# MCU.net
KiCad netlist of a schematic drawn in Altium Designer
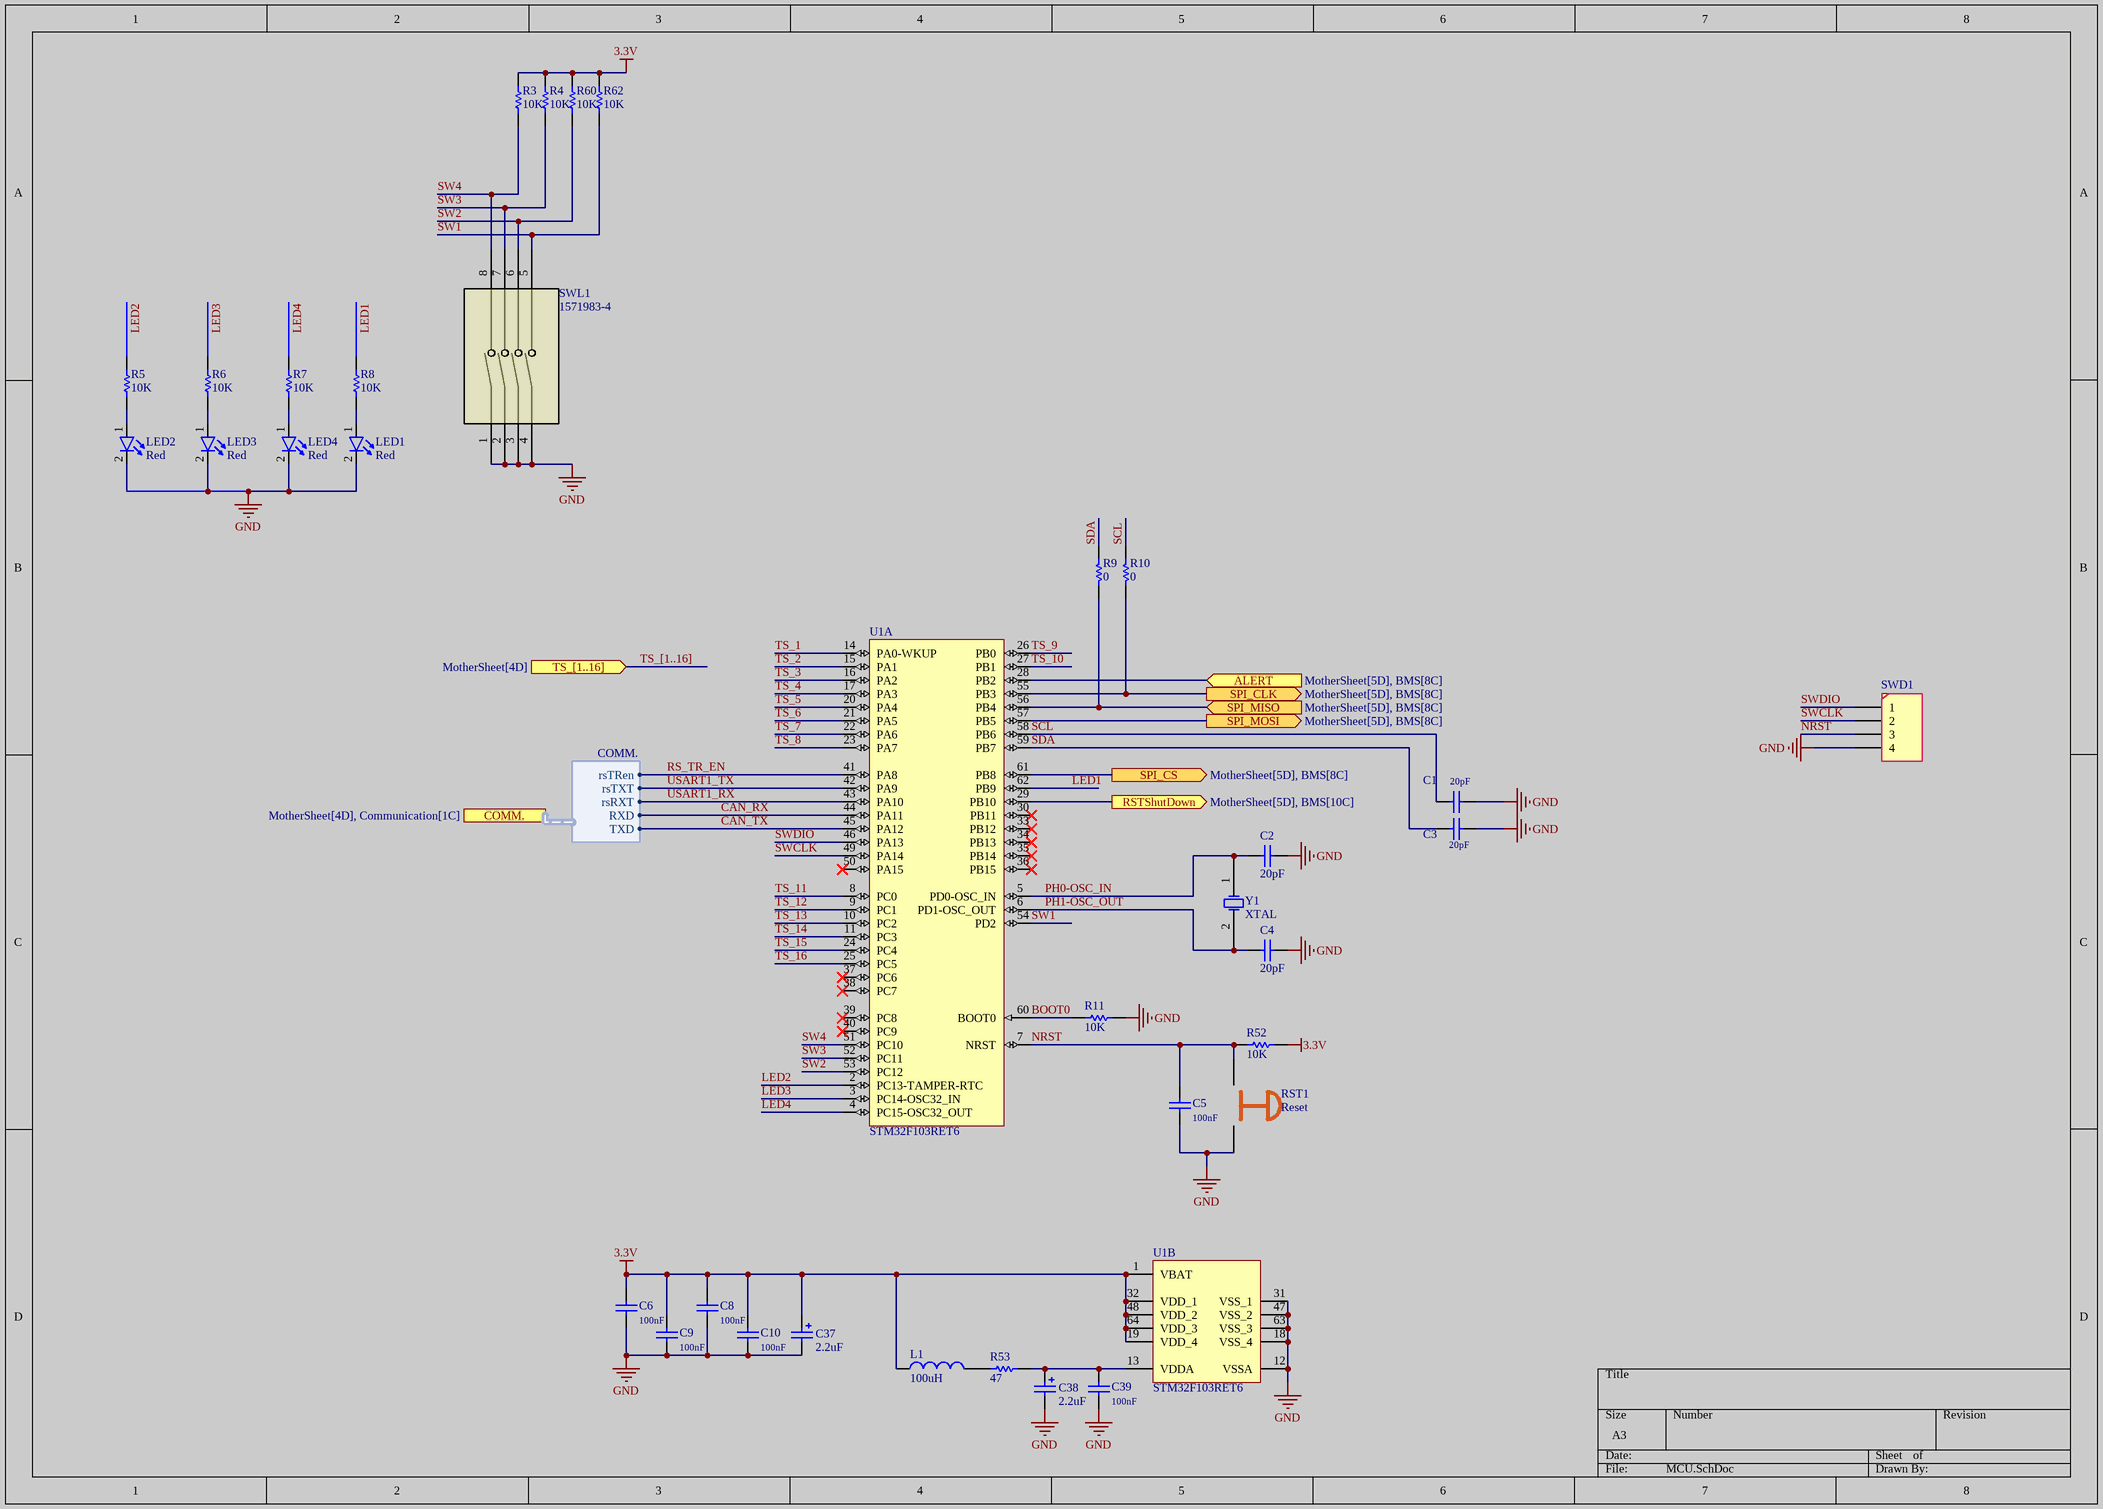
[diagram p0: MCU.SchDoc]

(export (version "E")
  (design (tool "Eeschema 10.0.6"))
  (components
    (comp (ref "C1")
      (value "20pF")
      (footprint "CAPC0603")
      (description "Capacitor")
      (fields (field (name "PUBLISHER") "Altium Limited"))
      (libsource (lib "eLIB") (part "Capacitor"))
    )
    (comp (ref "C2")
      (value "20pF")
      (footprint "CAPC0603")
      (description "Capacitor")
      (fields (field (name "PUBLISHER") "Altium Limited"))
      (libsource (lib "eLIB") (part "Capacitor"))
    )
    (comp (ref "C3")
      (value "20pF")
      (footprint "CAPC0603")
      (description "Capacitor")
      (fields (field (name "PUBLISHER") "Altium Limited"))
      (libsource (lib "eLIB") (part "Capacitor"))
    )
    (comp (ref "C4")
      (value "20pF")
      (footprint "CAPC0603")
      (description "Capacitor")
      (fields (field (name "PUBLISHER") "Altium Limited"))
      (libsource (lib "eLIB") (part "Capacitor"))
    )
    (comp (ref "C5")
      (value "100nF")
      (footprint "CAPC0603")
      (description "Capacitor")
      (fields (field (name "PUBLISHER") "Altium Limited"))
      (libsource (lib "eLIB") (part "Capacitor"))
    )
    (comp (ref "C6")
      (value "100nF")
      (footprint "CAPC0603")
      (description "Capacitor")
      (fields (field (name "PUBLISHER") "Altium Limited"))
      (libsource (lib "eLIB") (part "Capacitor"))
    )
    (comp (ref "C8")
      (value "100nF")
      (footprint "CAPC0603")
      (description "Capacitor")
      (fields (field (name "PUBLISHER") "Altium Limited"))
      (libsource (lib "eLIB") (part "Capacitor"))
    )
    (comp (ref "C9")
      (value "100nF")
      (footprint "CAPC0603")
      (description "Capacitor")
      (fields (field (name "PUBLISHER") "Altium Limited"))
      (libsource (lib "eLIB") (part "Capacitor"))
    )
    (comp (ref "C10")
      (value "100nF")
      (footprint "CAPC0603")
      (description "Capacitor")
      (fields (field (name "PUBLISHER") "Altium Limited"))
      (libsource (lib "eLIB") (part "Capacitor"))
    )
    (comp (ref "C37")
      (value "2.2uF")
      (footprint "CAP1206")
      (description "Tantalium Capacitor Size C")
      (fields (field (name "PUBLISHER") "Altium Limited"))
      (libsource (lib "eLIB") (part "Cap_Tan"))
    )
    (comp (ref "C38")
      (value "2.2uF")
      (footprint "CAP1206")
      (description "Tantalium Capacitor Size C")
      (fields (field (name "PUBLISHER") "Altium Limited"))
      (libsource (lib "eLIB") (part "Cap_Tan"))
    )
    (comp (ref "C39")
      (value "100nF")
      (footprint "CAPC0603")
      (description "Capacitor")
      (fields (field (name "PUBLISHER") "Altium Limited"))
      (libsource (lib "eLIB") (part "Capacitor"))
    )
    (comp (ref "L1")
      (value "100uH")
      (footprint "RES1206")
      (fields (field (name "PUBLISHER") "Altium Limited"))
      (libsource (lib "eLIB") (part "INDUCTOR"))
    )
    (comp (ref "LED1")
      (value "Red")
      (footprint "LED")
      (description "LED")
      (fields (field (name "COLOR") "Red") (field (name "DESIGNER") "Saeid Jorablo"))
      (libsource (lib "TaraSchlib") (part "LED"))
    )
    (comp (ref "LED2")
      (value "Red")
      (footprint "LED")
      (description "LED")
      (fields (field (name "COLOR") "Red") (field (name "DESIGNER") "Saeid Jorablo"))
      (libsource (lib "TaraSchlib") (part "LED"))
    )
    (comp (ref "LED3")
      (value "Red")
      (footprint "LED")
      (description "LED")
      (fields (field (name "COLOR") "Red") (field (name "DESIGNER") "Saeid Jorablo"))
      (libsource (lib "TaraSchlib") (part "LED"))
    )
    (comp (ref "LED4")
      (value "Red")
      (footprint "LED")
      (description "LED")
      (fields (field (name "COLOR") "Red") (field (name "DESIGNER") "Saeid Jorablo"))
      (libsource (lib "TaraSchlib") (part "LED"))
    )
    (comp (ref "R3")
      (value "10K")
      (footprint "RES0603")
      (description "0603,0.1W")
      (fields (field (name "PUBLISHER") "Altium Limited"))
      (libsource (lib "eLIB") (part "Resistor"))
    )
    (comp (ref "R4")
      (value "10K")
      (footprint "RES0603")
      (description "0603,0.1W")
      (fields (field (name "PUBLISHER") "Altium Limited"))
      (libsource (lib "eLIB") (part "Resistor"))
    )
    (comp (ref "R5")
      (value "10K")
      (footprint "RESC0603")
      (description "0603,0.1W")
      (fields (field (name "PUBLISHER") "Altium Limited"))
      (libsource (lib "eLIB") (part "Resistor"))
    )
    (comp (ref "R6")
      (value "10K")
      (footprint "RESC0603")
      (description "0603,0.1W")
      (fields (field (name "PUBLISHER") "Altium Limited"))
      (libsource (lib "eLIB") (part "Resistor"))
    )
    (comp (ref "R7")
      (value "10K")
      (footprint "RESC0603")
      (description "0603,0.1W")
      (fields (field (name "PUBLISHER") "Altium Limited"))
      (libsource (lib "eLIB") (part "Resistor"))
    )
    (comp (ref "R8")
      (value "10K")
      (footprint "RESC0603")
      (description "0603,0.1W")
      (fields (field (name "PUBLISHER") "Altium Limited"))
      (libsource (lib "eLIB") (part "Resistor"))
    )
    (comp (ref "R9")
      (value "0")
      (footprint "RESC0603")
      (description "0603,0.1W")
      (fields (field (name "PUBLISHER") "Altium Limited"))
      (libsource (lib "eLIB") (part "Resistor"))
    )
    (comp (ref "R10")
      (value "0")
      (footprint "RESC0603")
      (description "0603,0.1W")
      (fields (field (name "PUBLISHER") "Altium Limited"))
      (libsource (lib "eLIB") (part "Resistor"))
    )
    (comp (ref "R11")
      (value "10K")
      (footprint "RESC0603")
      (description "0603,0.1W")
      (fields (field (name "PUBLISHER") "Altium Limited"))
      (libsource (lib "eLIB") (part "Resistor"))
    )
    (comp (ref "R52")
      (value "10K")
      (footprint "RESC0603")
      (description "0603,0.1W")
      (fields (field (name "PUBLISHER") "Altium Limited"))
      (libsource (lib "eLIB") (part "Resistor"))
    )
    (comp (ref "R53")
      (value "47")
      (footprint "RESC0603")
      (description "0603,0.1W")
      (fields (field (name "PUBLISHER") "Altium Limited"))
      (libsource (lib "eLIB") (part "Resistor"))
    )
    (comp (ref "R60")
      (value "10K")
      (footprint "RES0603")
      (description "0603,0.1W")
      (fields (field (name "PUBLISHER") "Altium Limited"))
      (libsource (lib "eLIB") (part "Resistor"))
    )
    (comp (ref "R62")
      (value "10K")
      (footprint "RES0603")
      (description "0603,0.1W")
      (fields (field (name "PUBLISHER") "Altium Limited"))
      (libsource (lib "eLIB") (part "Resistor"))
    )
    (comp (ref "RST1")
      (value "Reset")
      (footprint "SWITCH-PB4")
      (description "4-Pin Push Button")
      (libsource (lib "eLIB") (part "Swtich-PB4"))
    )
    (comp (ref "SWD1")
      (value "~")
      (footprint "PIN HEADER 1*4 MALE")
      (description "Header, 4-Pin")
      (libsource (lib "eLIB") (part "Header1*4"))
    )
    (comp (ref "SWL1")
      (value "1571983-4")
      (footprint "SW4_1571983_4P_TEC")
      (description "GDH04S04=DIP SWITCH")
      (fields (field (name "COPYRIGHT") "Copyright (C) 2025 Ultra Librarian. All rights reserved."))
      (libsource (lib "SINA") (part "1571983-4"))
    )
    (comp (ref "U1")
      (value "STM32F103RET6")
      (footprint "LQFP, 64")
      (libsource (lib "SINA") (part "STM32F103RET6"))
    )
    (comp (ref "Y1") (value "XTAL") (footprint "XTAL") (libsource (lib "eLIB") (part "XTAL")))
  )
  (nets
    (net (code "2") (name "/ALERT") (class "Default")
      (node (ref "U1") (pin "28") (pinfunction "PB2_28") (pintype "bidirectional"))
    )
    (net (code "3") (name "/BOOT0") (class "Default")
      (node (ref "R11") (pin "2") (pinfunction "2_2") (pintype "passive"))
      (node (ref "U1") (pin "60") (pinfunction "BOOT0_60") (pintype "input"))
    )
    (net (code "4") (name "/CAN_RX") (class "Default")
      (node (ref "U1") (pin "44") (pinfunction "PA11_44") (pintype "bidirectional"))
    )
    (net (code "5") (name "/CAN_TX") (class "Default")
      (node (ref "U1") (pin "45") (pinfunction "PA12_45") (pintype "bidirectional"))
    )
    (net (code "6") (name "/LED1") (class "Default")
      (node (ref "R8") (pin "2") (pinfunction "2_2") (pintype "passive"))
      (node (ref "U1") (pin "62") (pinfunction "PB9_62") (pintype "bidirectional"))
    )
    (net (code "7") (name "/LED2") (class "Default")
      (node (ref "R5") (pin "2") (pinfunction "2_2") (pintype "passive"))
      (node (ref "U1") (pin "2") (pinfunction "PC13-TAMPER-RTC_2") (pintype "bidirectional"))
    )
    (net (code "8") (name "/LED3") (class "Default")
      (node (ref "R6") (pin "2") (pinfunction "2_2") (pintype "passive"))
      (node (ref "U1") (pin "3") (pinfunction "PC14-OSC32_IN_3") (pintype "bidirectional"))
    )
    (net (code "9") (name "/LED4") (class "Default")
      (node (ref "R7") (pin "2") (pinfunction "2_2") (pintype "passive"))
      (node (ref "U1") (pin "4") (pinfunction "PC15-OSC32_OUT_4") (pintype "bidirectional"))
    )
    (net (code "10") (name "/NRST") (class "Default")
      (node (ref "C5") (pin "1") (pinfunction "1_1") (pintype "passive"))
      (node (ref "R52") (pin "1") (pinfunction "1_1") (pintype "passive"))
      (node (ref "RST1") (pin "1") (pinfunction "1_1") (pintype "passive"))
      (node (ref "SWD1") (pin "3") (pinfunction "3_3") (pintype "passive"))
      (node (ref "U1") (pin "7") (pinfunction "NRST_7") (pintype "bidirectional"))
    )
    (net (code "11") (name "/PH0-OSC_IN") (class "Default")
      (node (ref "C2") (pin "2") (pinfunction "2_2") (pintype "passive"))
      (node (ref "U1") (pin "5") (pinfunction "PD0-OSC_IN_5") (pintype "bidirectional"))
      (node (ref "Y1") (pin "1") (pinfunction "1_1") (pintype "passive"))
    )
    (net (code "12") (name "/PH1-OSC_OUT") (class "Default")
      (node (ref "C4") (pin "2") (pinfunction "2_2") (pintype "passive"))
      (node (ref "U1") (pin "6") (pinfunction "PD1-OSC_OUT_6") (pintype "bidirectional"))
      (node (ref "Y1") (pin "2") (pinfunction "2_2") (pintype "passive"))
    )
    (net (code "13") (name "/RSTShutDown") (class "Default")
      (node (ref "U1") (pin "29") (pinfunction "PB10_29") (pintype "bidirectional"))
    )
    (net (code "14") (name "/RS_TR_EN") (class "Default")
      (node (ref "U1") (pin "41") (pinfunction "PA8_41") (pintype "bidirectional"))
    )
    (net (code "15") (name "/SCL") (class "Default")
      (node (ref "C1") (pin "1") (pinfunction "1_1") (pintype "passive"))
      (node (ref "R10") (pin "1") (pinfunction "1_1") (pintype "passive"))
      (node (ref "U1") (pin "58") (pinfunction "PB6_58") (pintype "bidirectional"))
    )
    (net (code "16") (name "/SDA") (class "Default")
      (node (ref "C3") (pin "1") (pinfunction "1_1") (pintype "passive"))
      (node (ref "R9") (pin "1") (pinfunction "1_1") (pintype "passive"))
      (node (ref "U1") (pin "59") (pinfunction "PB7_59") (pintype "bidirectional"))
    )
    (net (code "17") (name "/SPI_CLK") (class "Default")
      (node (ref "R10") (pin "2") (pinfunction "2_2") (pintype "passive"))
      (node (ref "U1") (pin "55") (pinfunction "PB3_55") (pintype "bidirectional"))
    )
    (net (code "18") (name "/SPI_CS") (class "Default")
      (node (ref "U1") (pin "61") (pinfunction "PB8_61") (pintype "bidirectional"))
    )
    (net (code "19") (name "/SPI_MISO") (class "Default")
      (node (ref "R9") (pin "2") (pinfunction "2_2") (pintype "passive"))
      (node (ref "U1") (pin "56") (pinfunction "PB4_56") (pintype "bidirectional"))
    )
    (net (code "20") (name "/SPI_MOSI") (class "Default")
      (node (ref "U1") (pin "57") (pinfunction "PB5_57") (pintype "bidirectional"))
    )
    (net (code "21") (name "/SW1") (class "Default")
      (node (ref "R62") (pin "1") (pinfunction "1_1") (pintype "passive"))
      (node (ref "SWL1") (pin "5") (pinfunction "5_5") (pintype "passive"))
      (node (ref "U1") (pin "54") (pinfunction "PD2_54") (pintype "bidirectional"))
    )
    (net (code "22") (name "/SW2") (class "Default")
      (node (ref "R60") (pin "1") (pinfunction "1_1") (pintype "passive"))
      (node (ref "SWL1") (pin "6") (pinfunction "6_6") (pintype "passive"))
      (node (ref "U1") (pin "53") (pinfunction "PC12_53") (pintype "bidirectional"))
    )
    (net (code "23") (name "/SW3") (class "Default")
      (node (ref "R4") (pin "1") (pinfunction "1_1") (pintype "passive"))
      (node (ref "SWL1") (pin "7") (pinfunction "7_7") (pintype "passive"))
      (node (ref "U1") (pin "52") (pinfunction "PC11_52") (pintype "bidirectional"))
    )
    (net (code "24") (name "/SW4") (class "Default")
      (node (ref "R3") (pin "1") (pinfunction "1_1") (pintype "passive"))
      (node (ref "SWL1") (pin "8") (pinfunction "8_8") (pintype "passive"))
      (node (ref "U1") (pin "51") (pinfunction "PC10_51") (pintype "bidirectional"))
    )
    (net (code "25") (name "/SWCLK") (class "Default")
      (node (ref "SWD1") (pin "2") (pinfunction "2_2") (pintype "passive"))
      (node (ref "U1") (pin "49") (pinfunction "PA14_49") (pintype "bidirectional"))
    )
    (net (code "26") (name "/SWDIO") (class "Default")
      (node (ref "SWD1") (pin "1") (pinfunction "1_1") (pintype "passive"))
      (node (ref "U1") (pin "46") (pinfunction "PA13_46") (pintype "bidirectional"))
    )
    (net (code "27") (name "/TS_1") (class "Default")
      (node (ref "U1") (pin "14") (pinfunction "PA0-WKUP_14") (pintype "bidirectional"))
    )
    (net (code "28") (name "/TS_2") (class "Default")
      (node (ref "U1") (pin "15") (pinfunction "PA1_15") (pintype "bidirectional"))
    )
    (net (code "29") (name "/TS_3") (class "Default")
      (node (ref "U1") (pin "16") (pinfunction "PA2_16") (pintype "bidirectional"))
    )
    (net (code "30") (name "/TS_4") (class "Default")
      (node (ref "U1") (pin "17") (pinfunction "PA3_17") (pintype "bidirectional"))
    )
    (net (code "31") (name "/TS_5") (class "Default")
      (node (ref "U1") (pin "20") (pinfunction "PA4_20") (pintype "bidirectional"))
    )
    (net (code "32") (name "/TS_6") (class "Default")
      (node (ref "U1") (pin "21") (pinfunction "PA5_21") (pintype "bidirectional"))
    )
    (net (code "33") (name "/TS_7") (class "Default")
      (node (ref "U1") (pin "22") (pinfunction "PA6_22") (pintype "bidirectional"))
    )
    (net (code "34") (name "/TS_8") (class "Default")
      (node (ref "U1") (pin "23") (pinfunction "PA7_23") (pintype "bidirectional"))
    )
    (net (code "35") (name "/TS_9") (class "Default")
      (node (ref "U1") (pin "26") (pinfunction "PB0_26") (pintype "bidirectional"))
    )
    (net (code "36") (name "/TS_10") (class "Default")
      (node (ref "U1") (pin "27") (pinfunction "PB1_27") (pintype "bidirectional"))
    )
    (net (code "37") (name "/TS_11") (class "Default")
      (node (ref "U1") (pin "8") (pinfunction "PC0_8") (pintype "bidirectional"))
    )
    (net (code "38") (name "/TS_12") (class "Default")
      (node (ref "U1") (pin "9") (pinfunction "PC1_9") (pintype "bidirectional"))
    )
    (net (code "39") (name "/TS_13") (class "Default")
      (node (ref "U1") (pin "10") (pinfunction "PC2_10") (pintype "bidirectional"))
    )
    (net (code "40") (name "/TS_14") (class "Default")
      (node (ref "U1") (pin "11") (pinfunction "PC3_11") (pintype "bidirectional"))
    )
    (net (code "41") (name "/TS_15") (class "Default")
      (node (ref "U1") (pin "24") (pinfunction "PC4_24") (pintype "bidirectional"))
    )
    (net (code "42") (name "/TS_16") (class "Default")
      (node (ref "U1") (pin "25") (pinfunction "PC5_25") (pintype "bidirectional"))
    )
    (net (code "44") (name "/USART1_RX") (class "Default")
      (node (ref "U1") (pin "43") (pinfunction "PA10_43") (pintype "bidirectional"))
    )
    (net (code "45") (name "/USART1_TX") (class "Default")
      (node (ref "U1") (pin "42") (pinfunction "PA9_42") (pintype "bidirectional"))
    )
    (net (code "47") (name "3.3V") (class "Default")
      (node (ref "C10") (pin "1") (pinfunction "1_1") (pintype "passive"))
      (node (ref "C37") (pin "1") (pinfunction "1_1") (pintype "passive"))
      (node (ref "C6") (pin "1") (pinfunction "1_1") (pintype "passive"))
      (node (ref "C8") (pin "1") (pinfunction "1_1") (pintype "passive"))
      (node (ref "C9") (pin "1") (pinfunction "1_1") (pintype "passive"))
      (node (ref "L1") (pin "1") (pinfunction "1_1") (pintype "passive"))
      (node (ref "R3") (pin "2") (pinfunction "2_2") (pintype "passive"))
      (node (ref "R4") (pin "2") (pinfunction "2_2") (pintype "passive"))
      (node (ref "R52") (pin "2") (pinfunction "2_2") (pintype "passive"))
      (node (ref "R60") (pin "2") (pinfunction "2_2") (pintype "passive"))
      (node (ref "R62") (pin "2") (pinfunction "2_2") (pintype "passive"))
      (node (ref "U1") (pin "1") (pinfunction "VBAT_1") (pintype "power_in"))
      (node (ref "U1") (pin "19") (pinfunction "VDD_4_19") (pintype "power_in"))
      (node (ref "U1") (pin "32") (pinfunction "VDD_1_32") (pintype "power_in"))
      (node (ref "U1") (pin "48") (pinfunction "VDD_2_48") (pintype "power_in"))
      (node (ref "U1") (pin "64") (pinfunction "VDD_3_64") (pintype "power_in"))
    )
    (net (code "48") (name "GND") (class "Default")
      (node (ref "C1") (pin "2") (pinfunction "2_2") (pintype "passive"))
      (node (ref "C10") (pin "2") (pinfunction "2_2") (pintype "passive"))
      (node (ref "C2") (pin "1") (pinfunction "1_1") (pintype "passive"))
      (node (ref "C3") (pin "2") (pinfunction "2_2") (pintype "passive"))
      (node (ref "C37") (pin "2") (pinfunction "2_2") (pintype "passive"))
      (node (ref "C38") (pin "2") (pinfunction "2_2") (pintype "passive"))
      (node (ref "C39") (pin "2") (pinfunction "2_2") (pintype "passive"))
      (node (ref "C4") (pin "1") (pinfunction "1_1") (pintype "passive"))
      (node (ref "C5") (pin "2") (pinfunction "2_2") (pintype "passive"))
      (node (ref "C6") (pin "2") (pinfunction "2_2") (pintype "passive"))
      (node (ref "C8") (pin "2") (pinfunction "2_2") (pintype "passive"))
      (node (ref "C9") (pin "2") (pinfunction "2_2") (pintype "passive"))
      (node (ref "LED1") (pin "2") (pinfunction "K_2") (pintype "passive"))
      (node (ref "LED2") (pin "2") (pinfunction "K_2") (pintype "passive"))
      (node (ref "LED3") (pin "2") (pinfunction "K_2") (pintype "passive"))
      (node (ref "LED4") (pin "2") (pinfunction "K_2") (pintype "passive"))
      (node (ref "R11") (pin "1") (pinfunction "1_1") (pintype "passive"))
      (node (ref "RST1") (pin "2") (pinfunction "2_2") (pintype "passive"))
      (node (ref "SWD1") (pin "4") (pinfunction "4_4") (pintype "passive"))
      (node (ref "SWL1") (pin "1") (pinfunction "1_1") (pintype "passive"))
      (node (ref "SWL1") (pin "2") (pinfunction "2_2") (pintype "passive"))
      (node (ref "SWL1") (pin "3") (pinfunction "3_3") (pintype "passive"))
      (node (ref "SWL1") (pin "4") (pinfunction "4_4") (pintype "passive"))
      (node (ref "U1") (pin "12") (pinfunction "VSSA_12") (pintype "power_in"))
      (node (ref "U1") (pin "18") (pinfunction "VSS_4_18") (pintype "power_in"))
      (node (ref "U1") (pin "31") (pinfunction "VSS_1_31") (pintype "power_in"))
      (node (ref "U1") (pin "47") (pinfunction "VSS_2_47") (pintype "power_in"))
      (node (ref "U1") (pin "63") (pinfunction "VSS_3_63") (pintype "power_in"))
    )
    (net (code "49") (name "Net-(L1-Pad2)") (class "Default")
      (node (ref "L1") (pin "2") (pinfunction "2_2") (pintype "passive"))
      (node (ref "R53") (pin "2") (pinfunction "2_2") (pintype "passive"))
    )
    (net (code "50") (name "Net-(LED1-A)") (class "Default")
      (node (ref "LED1") (pin "1") (pinfunction "A_1") (pintype "passive"))
      (node (ref "R8") (pin "1") (pinfunction "1_1") (pintype "passive"))
    )
    (net (code "51") (name "Net-(LED2-A)") (class "Default")
      (node (ref "LED2") (pin "1") (pinfunction "A_1") (pintype "passive"))
      (node (ref "R5") (pin "1") (pinfunction "1_1") (pintype "passive"))
    )
    (net (code "52") (name "Net-(LED3-A)") (class "Default")
      (node (ref "LED3") (pin "1") (pinfunction "A_1") (pintype "passive"))
      (node (ref "R6") (pin "1") (pinfunction "1_1") (pintype "passive"))
    )
    (net (code "53") (name "Net-(LED4-A)") (class "Default")
      (node (ref "LED4") (pin "1") (pinfunction "A_1") (pintype "passive"))
      (node (ref "R7") (pin "1") (pinfunction "1_1") (pintype "passive"))
    )
    (net (code "54") (name "Net-(U1B-VDDA)") (class "Default")
      (node (ref "C38") (pin "1") (pinfunction "1_1") (pintype "passive"))
      (node (ref "C39") (pin "1") (pinfunction "1_1") (pintype "passive"))
      (node (ref "R53") (pin "1") (pinfunction "1_1") (pintype "passive"))
      (node (ref "U1") (pin "13") (pinfunction "VDDA_13") (pintype "power_in"))
    )
    (net (code "55") (name "unconnected-(U1A-PA15-Pad50)") (class "Default")
      (node (ref "U1") (pin "50") (pinfunction "PA15_50") (pintype "bidirectional+no_connect"))
    )
    (net (code "56") (name "unconnected-(U1A-PB11-Pad30)") (class "Default")
      (node (ref "U1") (pin "30") (pinfunction "PB11_30") (pintype "bidirectional+no_connect"))
    )
    (net (code "57") (name "unconnected-(U1A-PB12-Pad33)") (class "Default")
      (node (ref "U1") (pin "33") (pinfunction "PB12_33") (pintype "bidirectional+no_connect"))
    )
    (net (code "58") (name "unconnected-(U1A-PB13-Pad34)") (class "Default")
      (node (ref "U1") (pin "34") (pinfunction "PB13_34") (pintype "bidirectional+no_connect"))
    )
    (net (code "59") (name "unconnected-(U1A-PB14-Pad35)") (class "Default")
      (node (ref "U1") (pin "35") (pinfunction "PB14_35") (pintype "bidirectional+no_connect"))
    )
    (net (code "60") (name "unconnected-(U1A-PB15-Pad36)") (class "Default")
      (node (ref "U1") (pin "36") (pinfunction "PB15_36") (pintype "bidirectional+no_connect"))
    )
    (net (code "61") (name "unconnected-(U1A-PC6-Pad37)") (class "Default")
      (node (ref "U1") (pin "37") (pinfunction "PC6_37") (pintype "bidirectional+no_connect"))
    )
    (net (code "62") (name "unconnected-(U1A-PC7-Pad38)") (class "Default")
      (node (ref "U1") (pin "38") (pinfunction "PC7_38") (pintype "bidirectional+no_connect"))
    )
    (net (code "63") (name "unconnected-(U1A-PC8-Pad39)") (class "Default")
      (node (ref "U1") (pin "39") (pinfunction "PC8_39") (pintype "bidirectional+no_connect"))
    )
    (net (code "64") (name "unconnected-(U1A-PC9-Pad40)") (class "Default")
      (node (ref "U1") (pin "40") (pinfunction "PC9_40") (pintype "bidirectional+no_connect"))
    )
  )
)
